# Adafruit_AS7341.net
KiCad netlist of a schematic drawn in EAGLE
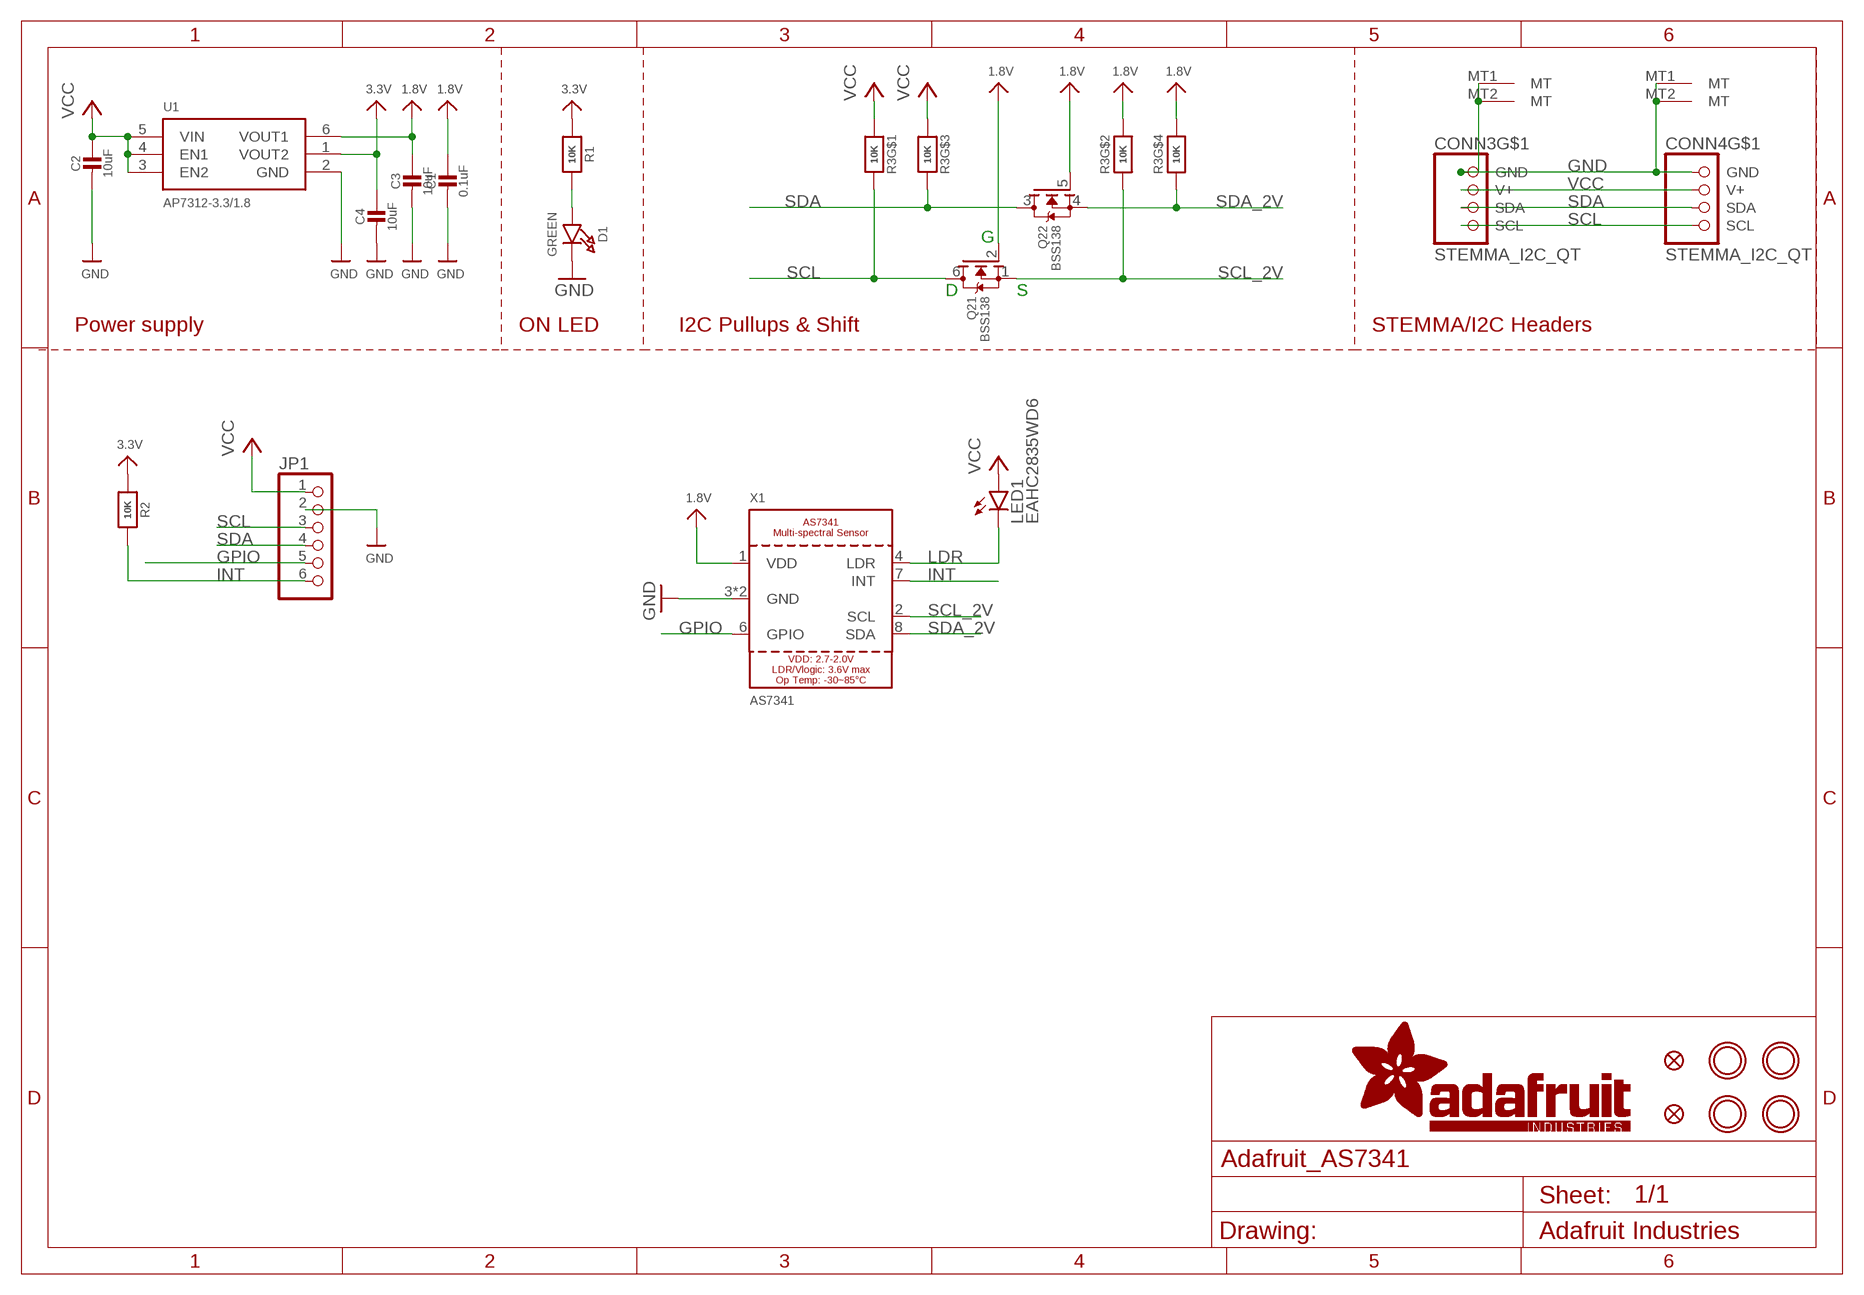
[diagram p0: schematic, sheet 1]

(export (version "E")
  (design (tool "Eeschema 10.0.6"))
  (components
    (comp (ref "C1")
      (value "0.1uF")
      (footprint "eagle-import:0603-NO")
      (libsource (lib "eagle-import") (part "CAP_CERAMIC0603_NO"))
    )
    (comp (ref "C2")
      (value "10uF")
      (footprint "eagle-import:0805-NO")
      (libsource (lib "eagle-import") (part "CAP_CERAMIC0805-NOOUTLINE"))
    )
    (comp (ref "C3")
      (value "10uF")
      (footprint "eagle-import:0805-NO")
      (libsource (lib "eagle-import") (part "CAP_CERAMIC0805-NOOUTLINE"))
    )
    (comp (ref "C4")
      (value "10uF")
      (footprint "eagle-import:0805-NO")
      (libsource (lib "eagle-import") (part "CAP_CERAMIC0805-NOOUTLINE"))
    )
    (comp (ref "CONN3")
      (value "STEMMA_I2C_QT")
      (footprint "eagle-import:JST_SH4")
      (libsource (lib "eagle-import") (part "STEMMA_I2C_QT"))
    )
    (comp (ref "CONN4")
      (value "STEMMA_I2C_QT")
      (footprint "eagle-import:JST_SH4")
      (libsource (lib "eagle-import") (part "STEMMA_I2C_QT"))
    )
    (comp (ref "D1")
      (value "GREEN")
      (footprint "eagle-import:CHIPLED_0603_NOOUTLINE")
      (libsource (lib "eagle-import") (part "LED0603_NOOUTLINE"))
    )
    (comp (ref "FID3")
      (value "FIDUCIAL_1MM")
      (footprint "eagle-import:FIDUCIAL_1MM")
      (libsource (lib "eagle-import") (part "FIDUCIAL_1MM"))
    )
    (comp (ref "FID4")
      (value "FIDUCIAL_1MM")
      (footprint "eagle-import:FIDUCIAL_1MM")
      (libsource (lib "eagle-import") (part "FIDUCIAL_1MM"))
    )
    (comp (ref "JP1")
      (value "HEADER-1X670MIL")
      (footprint "eagle-import:1X06_ROUND_70")
      (libsource (lib "eagle-import") (part "HEADER-1X670MIL"))
    )
    (comp (ref "LED1")
      (value "EAHC2835WD6")
      (footprint "eagle-import:KA-3528ASYC")
      (libsource (lib "eagle-import") (part "LEDKA-3528ASYC"))
    )
    (comp (ref "Q2")
      (value "BSS138")
      (footprint "eagle-import:SOT363")
      (libsource (lib "eagle-import") (part "MOSFET-N_DUAL"))
    )
    (comp (ref "R1")
      (value "10K")
      (footprint "eagle-import:0603-NO")
      (libsource (lib "eagle-import") (part "RESISTOR_0603_NOOUT"))
    )
    (comp (ref "R2")
      (value "10K")
      (footprint "eagle-import:0603-NO")
      (libsource (lib "eagle-import") (part "RESISTOR_0603_NOOUT"))
    )
    (comp (ref "R3")
      (value "10K")
      (footprint "eagle-import:RESPACK_4X0603")
      (libsource (lib "eagle-import") (part "RESISTOR_4PACK"))
    )
    (comp (ref "U$1")
      (value "MOUNTINGHOLE2.5")
      (footprint "eagle-import:MOUNTINGHOLE_2.5_PLATED")
      (libsource (lib "eagle-import") (part "MOUNTINGHOLE2.5"))
    )
    (comp (ref "U$17")
      (value "MOUNTINGHOLE2.5")
      (footprint "eagle-import:MOUNTINGHOLE_2.5_PLATED")
      (libsource (lib "eagle-import") (part "MOUNTINGHOLE2.5"))
    )
    (comp (ref "U$19")
      (value "MOUNTINGHOLE2.5")
      (footprint "eagle-import:MOUNTINGHOLE_2.5_PLATED")
      (libsource (lib "eagle-import") (part "MOUNTINGHOLE2.5"))
    )
    (comp (ref "U$21")
      (value "MOUNTINGHOLE2.5")
      (footprint "eagle-import:MOUNTINGHOLE_2.5_PLATED")
      (libsource (lib "eagle-import") (part "MOUNTINGHOLE2.5"))
    )
    (comp (ref "U1")
      (value "AP7312-3.3/1.8")
      (footprint "eagle-import:SOT23-6")
      (libsource (lib "eagle-import") (part "VREG_SOT23-6_DUALAP7312"))
    )
    (comp (ref "X1")
      (value "AS7341")
      (footprint "eagle-import:AS7341")
      (libsource (lib "eagle-import") (part "AS7341"))
    )
  )
  (nets
    (net (code "1") (name "/GPIO") (class "Default")
      (node (ref "JP1") (pin "5") (pinfunction "5_5") (pintype "passive"))
      (node (ref "X1") (pin "6") (pinfunction "GPIO_6") (pintype "power_in"))
    )
    (net (code "2") (name "/INT") (class "Default")
      (node (ref "JP1") (pin "6") (pinfunction "6_6") (pintype "passive"))
      (node (ref "R2") (pin "2") (pinfunction "2_2") (pintype "passive"))
      (node (ref "X1") (pin "7") (pinfunction "INT_7") (pintype "output"))
    )
    (net (code "3") (name "/LDR") (class "Default")
      (node (ref "LED1") (pin "C") (pinfunction "C_C") (pintype "passive"))
      (node (ref "X1") (pin "4") (pinfunction "LDR_4") (pintype "bidirectional"))
    )
    (net (code "4") (name "/SCL") (class "Default")
      (node (ref "CONN3") (pin "4") (pinfunction "SCL_4") (pintype "passive"))
      (node (ref "CONN4") (pin "4") (pinfunction "SCL_4") (pintype "passive"))
      (node (ref "JP1") (pin "3") (pinfunction "3_3") (pintype "passive"))
      (node (ref "Q2") (pin "6") (pinfunction "D_6") (pintype "bidirectional"))
      (node (ref "R3") (pin "8") (pinfunction "2_8") (pintype "passive"))
    )
    (net (code "5") (name "/SCL_2V") (class "Default")
      (node (ref "Q2") (pin "1") (pinfunction "S_1") (pintype "bidirectional"))
      (node (ref "R3") (pin "7") (pinfunction "2_7") (pintype "passive"))
      (node (ref "X1") (pin "2") (pinfunction "SCL_2") (pintype "input"))
    )
    (net (code "6") (name "/SDA") (class "Default")
      (node (ref "CONN3") (pin "3") (pinfunction "SDA_3") (pintype "passive"))
      (node (ref "CONN4") (pin "3") (pinfunction "SDA_3") (pintype "passive"))
      (node (ref "JP1") (pin "4") (pinfunction "4_4") (pintype "passive"))
      (node (ref "Q2") (pin "3") (pinfunction "D_3") (pintype "bidirectional"))
      (node (ref "R3") (pin "6") (pinfunction "2_6") (pintype "passive"))
    )
    (net (code "7") (name "/SDA_2V") (class "Default")
      (node (ref "Q2") (pin "4") (pinfunction "S_4") (pintype "bidirectional"))
      (node (ref "R3") (pin "5") (pinfunction "2_5") (pintype "passive"))
      (node (ref "X1") (pin "8") (pinfunction "SDA_8") (pintype "bidirectional"))
    )
    (net (code "8") (name "1.8V") (class "Default")
      (node (ref "C1") (pin "1") (pinfunction "1_1") (pintype "passive"))
      (node (ref "C3") (pin "1") (pinfunction "1_1") (pintype "passive"))
      (node (ref "Q2") (pin "2") (pinfunction "G_2") (pintype "bidirectional"))
      (node (ref "Q2") (pin "5") (pinfunction "G_5") (pintype "bidirectional"))
      (node (ref "R3") (pin "2") (pinfunction "1_2") (pintype "passive"))
      (node (ref "R3") (pin "4") (pinfunction "1_4") (pintype "passive"))
      (node (ref "U1") (pin "6") (pinfunction "VOUT1_6") (pintype "bidirectional"))
      (node (ref "X1") (pin "1") (pinfunction "VDD_1") (pintype "power_in"))
    )
    (net (code "9") (name "3.3V") (class "Default")
      (node (ref "C4") (pin "1") (pinfunction "1_1") (pintype "passive"))
      (node (ref "R1") (pin "1") (pinfunction "1_1") (pintype "passive"))
      (node (ref "R2") (pin "1") (pinfunction "1_1") (pintype "passive"))
      (node (ref "U1") (pin "1") (pinfunction "VOUT2_1") (pintype "bidirectional"))
    )
    (net (code "10") (name "GND") (class "Default")
      (node (ref "C1") (pin "2") (pinfunction "2_2") (pintype "passive"))
      (node (ref "C2") (pin "2") (pinfunction "2_2") (pintype "passive"))
      (node (ref "C3") (pin "2") (pinfunction "2_2") (pintype "passive"))
      (node (ref "C4") (pin "2") (pinfunction "2_2") (pintype "passive"))
      (node (ref "CONN3") (pin "1") (pinfunction "GND_1") (pintype "passive"))
      (node (ref "CONN3") (pin "MT1") (pinfunction "MT_MT1") (pintype "bidirectional"))
      (node (ref "CONN3") (pin "MT2") (pinfunction "MT_MT2") (pintype "bidirectional"))
      (node (ref "CONN4") (pin "1") (pinfunction "GND_1") (pintype "passive"))
      (node (ref "CONN4") (pin "MT1") (pinfunction "MT_MT1") (pintype "bidirectional"))
      (node (ref "CONN4") (pin "MT2") (pinfunction "MT_MT2") (pintype "bidirectional"))
      (node (ref "D1") (pin "C") (pinfunction "C_C") (pintype "passive"))
      (node (ref "JP1") (pin "2") (pinfunction "2_2") (pintype "passive"))
      (node (ref "U1") (pin "2") (pinfunction "GND_2") (pintype "bidirectional"))
      (node (ref "X1") (pin "3") (pinfunction "GND_3") (pintype "power_in"))
      (node (ref "X1") (pin "5") (pinfunction "GND_5") (pintype "power_in"))
    )
    (net (code "11") (name "Net-(D1-PadA)") (class "Default")
      (node (ref "D1") (pin "A") (pinfunction "A_A") (pintype "passive"))
      (node (ref "R1") (pin "2") (pinfunction "2_2") (pintype "passive"))
    )
    (net (code "12") (name "VCC") (class "Default")
      (node (ref "C2") (pin "1") (pinfunction "1_1") (pintype "passive"))
      (node (ref "CONN3") (pin "2") (pinfunction "V+_2") (pintype "passive"))
      (node (ref "CONN4") (pin "2") (pinfunction "V+_2") (pintype "passive"))
      (node (ref "JP1") (pin "1") (pinfunction "1_1") (pintype "passive"))
      (node (ref "LED1") (pin "A") (pinfunction "A_A") (pintype "passive"))
      (node (ref "R3") (pin "1") (pinfunction "1_1") (pintype "passive"))
      (node (ref "R3") (pin "3") (pinfunction "1_3") (pintype "passive"))
      (node (ref "U1") (pin "3") (pinfunction "EN2_3") (pintype "bidirectional"))
      (node (ref "U1") (pin "4") (pinfunction "EN1_4") (pintype "bidirectional"))
      (node (ref "U1") (pin "5") (pinfunction "VIN_5") (pintype "bidirectional"))
    )
  )
)
